# displayBoard.net
KiCad netlist of a schematic drawn in EAGLE
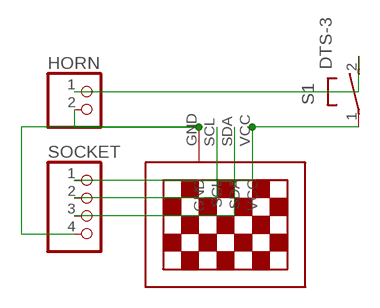
[diagram p0: schematic, sheet 1]

(export (version "E")
  (design (tool "Eeschema 10.0.6"))
  (components
    (comp (ref "HORN")
      (value "PINHD-1X2")
      (footprint "eagle-import:1X02")
      (libsource (lib "eagle-import") (part "PINHD-1X2"))
    )
    (comp (ref "S1")
      (value "DTS-3")
      (footprint "eagle-import:DTS-3")
      (libsource (lib "eagle-import") (part "DTS-3"))
    )
    (comp (ref "SOCKET")
      (value "PINHD-1X4")
      (footprint "eagle-import:1X04")
      (libsource (lib "eagle-import") (part "PINHD-1X4"))
    )
    (comp (ref "U$1")
      (value "13\"OLED13\"OLED")
      (footprint "eagle-import:1.3_OLED")
      (libsource (lib "eagle-import") (part "13{dblquote}OLED13{dblquote}OLED"))
    )
  )
  (nets
    (net (code "1") (name "Net-(HORN-Pad1)") (class "Default")
      (node (ref "HORN") (pin "1") (pinfunction "1_1") (pintype "passive"))
      (node (ref "S1") (pin "2") (pinfunction "2_2") (pintype "passive"))
    )
    (net (code "2") (name "Net-(HORN-Pad2)") (class "Default")
      (node (ref "HORN") (pin "2") (pinfunction "2_2") (pintype "passive"))
      (node (ref "SOCKET") (pin "4") (pinfunction "4_4") (pintype "passive"))
      (node (ref "U$1") (pin "GND") (pinfunction "GND_GND") (pintype "bidirectional"))
    )
    (net (code "3") (name "Net-(S1-Pad1)") (class "Default")
      (node (ref "S1") (pin "1") (pinfunction "1_1") (pintype "passive"))
      (node (ref "SOCKET") (pin "1") (pinfunction "1_1") (pintype "passive"))
      (node (ref "U$1") (pin "VCC") (pinfunction "VCC_VCC") (pintype "bidirectional"))
    )
    (net (code "4") (name "Net-(SOCKET-Pad2)") (class "Default")
      (node (ref "SOCKET") (pin "2") (pinfunction "2_2") (pintype "passive"))
      (node (ref "U$1") (pin "SCL") (pinfunction "SCL_SCL") (pintype "bidirectional"))
    )
    (net (code "5") (name "Net-(SOCKET-Pad3)") (class "Default")
      (node (ref "SOCKET") (pin "3") (pinfunction "3_3") (pintype "passive"))
      (node (ref "U$1") (pin "SDA") (pinfunction "SDA_SDA") (pintype "bidirectional"))
    )
  )
)
